# USB.net
KiCad netlist of a schematic drawn in Altium Designer
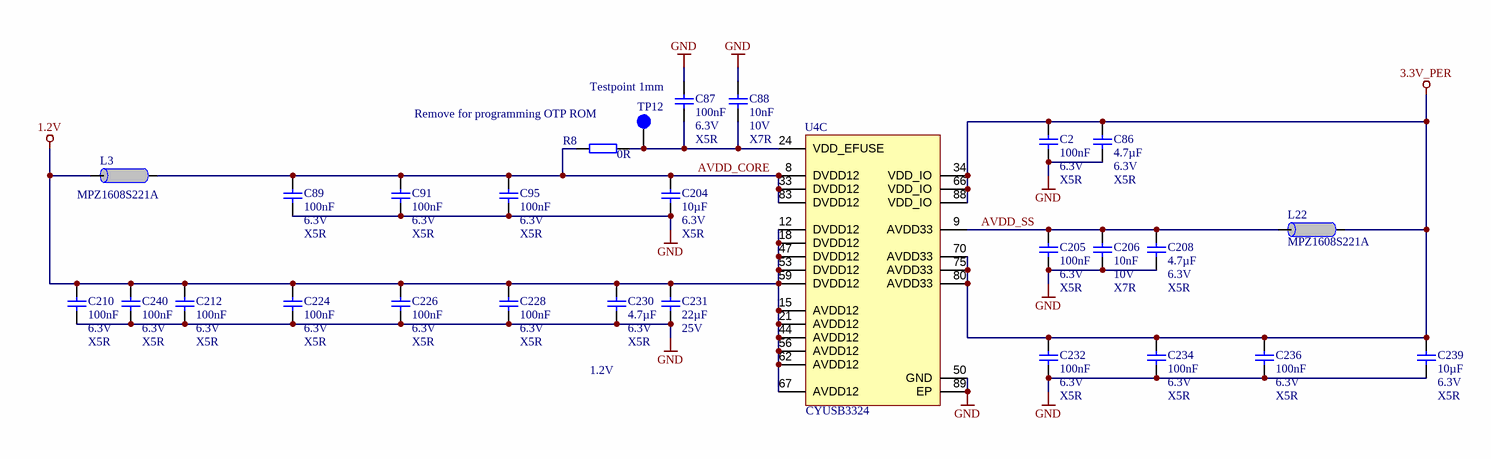
[diagram p0: USB.schdoc]

(export (version "E")
  (design (tool "Eeschema 10.0.6"))
  (components
    (comp (ref "C2")
      (value "100nF")
      (footprint "CAPC0603X33N")
      (description "KON 100nF 6.3V X5R SMD 10%")
      (fields
        (field (name "VOLTAGE") "6.3V")
        (field (name "TECHNOLOGY") "X5R")
        (field (name "TOLERANCE") "10%")
      )
      (libsource (lib "TE") (part "CAP-NP"))
    )
    (comp (ref "C86")
      (value "4.7µF")
      (footprint "CAPC1005X60N")
      (description "KON 4.7µF 6.3V X5R SMD 20%")
      (fields
        (field (name "VOLTAGE") "6.3V")
        (field (name "TECHNOLOGY") "X5R")
        (field (name "TOLERANCE") "20%")
      )
      (libsource (lib "TE") (part "CAP-NP"))
    )
    (comp (ref "C87")
      (value "100nF")
      (footprint "CAPC0603X33N")
      (description "KON 100nF 6.3V X5R SMD 10%")
      (fields
        (field (name "VOLTAGE") "6.3V")
        (field (name "TECHNOLOGY") "X5R")
        (field (name "TOLERANCE") "10%")
      )
      (libsource (lib "TE") (part "CAP-NP"))
    )
    (comp (ref "C88")
      (value "10nF")
      (footprint "CAPC0603X33N")
      (description "KON 10nF X7R 10V SMD 10%")
      (fields
        (field (name "VOLTAGE") "10V")
        (field (name "TECHNOLOGY") "X7R")
        (field (name "TOLERANCE") "10%")
      )
      (libsource (lib "TE") (part "CAP-NP"))
    )
    (comp (ref "C89")
      (value "100nF")
      (footprint "CAPC0603X33N")
      (description "KON 100nF 6.3V X5R SMD 10%")
      (fields
        (field (name "VOLTAGE") "6.3V")
        (field (name "TECHNOLOGY") "X5R")
        (field (name "TOLERANCE") "10%")
      )
      (libsource (lib "TE") (part "CAP-NP"))
    )
    (comp (ref "C91")
      (value "100nF")
      (footprint "CAPC0603X33N")
      (description "KON 100nF 6.3V X5R SMD 10%")
      (fields
        (field (name "VOLTAGE") "6.3V")
        (field (name "TECHNOLOGY") "X5R")
        (field (name "TOLERANCE") "10%")
      )
      (libsource (lib "TE") (part "CAP-NP"))
    )
    (comp (ref "C95")
      (value "100nF")
      (footprint "CAPC0603X33N")
      (description "KON 100nF 6.3V X5R SMD 10%")
      (fields
        (field (name "VOLTAGE") "6.3V")
        (field (name "TECHNOLOGY") "X5R")
        (field (name "TOLERANCE") "10%")
      )
      (libsource (lib "TE") (part "CAP-NP"))
    )
    (comp (ref "C204")
      (value "10µF")
      (footprint "CAPC1608X90N")
      (description "KON 10µF 6,3V X5R SMD")
      (fields (field (name "VOLTAGE") "6.3V") (field (name "TECHNOLOGY") "X5R"))
      (libsource (lib "TE") (part "CAP-NP"))
    )
    (comp (ref "C205")
      (value "100nF")
      (footprint "CAPC0603X33N")
      (description "KON 100nF 6.3V X5R SMD 10%")
      (fields
        (field (name "VOLTAGE") "6.3V")
        (field (name "TECHNOLOGY") "X5R")
        (field (name "TOLERANCE") "10%")
      )
      (libsource (lib "TE") (part "CAP-NP"))
    )
    (comp (ref "C206")
      (value "10nF")
      (footprint "CAPC0603X33N")
      (description "KON 10nF X7R 10V SMD 10%")
      (fields
        (field (name "VOLTAGE") "10V")
        (field (name "TECHNOLOGY") "X7R")
        (field (name "TOLERANCE") "10%")
      )
      (libsource (lib "TE") (part "CAP-NP"))
    )
    (comp (ref "C208")
      (value "4.7µF")
      (footprint "CAPC1005X60N")
      (description "KON 4.7µF 6.3V X5R SMD 20%")
      (fields
        (field (name "VOLTAGE") "6.3V")
        (field (name "TECHNOLOGY") "X5R")
        (field (name "TOLERANCE") "20%")
      )
      (libsource (lib "TE") (part "CAP-NP"))
    )
    (comp (ref "C210")
      (value "100nF")
      (footprint "CAPC0603X33N")
      (description "KON 100nF 6.3V X5R SMD 10%")
      (fields
        (field (name "VOLTAGE") "6.3V")
        (field (name "TECHNOLOGY") "X5R")
        (field (name "TOLERANCE") "10%")
      )
      (libsource (lib "TE") (part "CAP-NP"))
    )
    (comp (ref "C212")
      (value "100nF")
      (footprint "CAPC0603X33N")
      (description "KON 100nF 6.3V X5R SMD 10%")
      (fields
        (field (name "VOLTAGE") "6.3V")
        (field (name "TECHNOLOGY") "X5R")
        (field (name "TOLERANCE") "10%")
      )
      (libsource (lib "TE") (part "CAP-NP"))
    )
    (comp (ref "C224")
      (value "100nF")
      (footprint "CAPC0603X33N")
      (description "KON 100nF 6.3V X5R SMD 10%")
      (fields
        (field (name "VOLTAGE") "6.3V")
        (field (name "TECHNOLOGY") "X5R")
        (field (name "TOLERANCE") "10%")
      )
      (libsource (lib "TE") (part "CAP-NP"))
    )
    (comp (ref "C226")
      (value "100nF")
      (footprint "CAPC0603X33N")
      (description "KON 100nF 6.3V X5R SMD 10%")
      (fields
        (field (name "VOLTAGE") "6.3V")
        (field (name "TECHNOLOGY") "X5R")
        (field (name "TOLERANCE") "10%")
      )
      (libsource (lib "TE") (part "CAP-NP"))
    )
    (comp (ref "C228")
      (value "100nF")
      (footprint "CAPC0603X33N")
      (description "KON 100nF 6.3V X5R SMD 10%")
      (fields
        (field (name "VOLTAGE") "6.3V")
        (field (name "TECHNOLOGY") "X5R")
        (field (name "TOLERANCE") "10%")
      )
      (libsource (lib "TE") (part "CAP-NP"))
    )
    (comp (ref "C230")
      (value "4.7µF")
      (footprint "CAPC1005X60N")
      (description "KON 4.7µF 6.3V X5R SMD 20%")
      (fields
        (field (name "VOLTAGE") "6.3V")
        (field (name "TECHNOLOGY") "X5R")
        (field (name "TOLERANCE") "20%")
      )
      (libsource (lib "TE") (part "CAP-NP"))
    )
    (comp (ref "C231")
      (value "22µF")
      (footprint "CAPC3216X180N")
      (description "KON 22µF X5R 25V SMD 10%")
      (fields (field (name "VOLTAGE") "25V") (field (name "TOLERANCE") "10%"))
      (libsource (lib "TE") (part "CAP-NP"))
    )
    (comp (ref "C232")
      (value "100nF")
      (footprint "CAPC0603X33N")
      (description "KON 100nF 6.3V X5R SMD 10%")
      (fields
        (field (name "VOLTAGE") "6.3V")
        (field (name "TECHNOLOGY") "X5R")
        (field (name "TOLERANCE") "10%")
      )
      (libsource (lib "TE") (part "CAP-NP"))
    )
    (comp (ref "C234")
      (value "100nF")
      (footprint "CAPC0603X33N")
      (description "KON 100nF 6.3V X5R SMD 10%")
      (fields
        (field (name "VOLTAGE") "6.3V")
        (field (name "TECHNOLOGY") "X5R")
        (field (name "TOLERANCE") "10%")
      )
      (libsource (lib "TE") (part "CAP-NP"))
    )
    (comp (ref "C236")
      (value "100nF")
      (footprint "CAPC0603X33N")
      (description "KON 100nF 6.3V X5R SMD 10%")
      (fields
        (field (name "VOLTAGE") "6.3V")
        (field (name "TECHNOLOGY") "X5R")
        (field (name "TOLERANCE") "10%")
      )
      (libsource (lib "TE") (part "CAP-NP"))
    )
    (comp (ref "C239")
      (value "10µF")
      (footprint "CAPC1608X90N")
      (description "KON 10µF 6,3V X5R SMD")
      (fields (field (name "VOLTAGE") "6.3V") (field (name "TECHNOLOGY") "X5R"))
      (libsource (lib "TE") (part "CAP-NP"))
    )
    (comp (ref "C240")
      (value "100nF")
      (footprint "CAPC0603X33N")
      (description "KON 100nF 6.3V X5R SMD 10%")
      (fields
        (field (name "VOLTAGE") "6.3V")
        (field (name "TECHNOLOGY") "X5R")
        (field (name "TOLERANCE") "10%")
      )
      (libsource (lib "TE") (part "CAP-NP"))
    )
    (comp (ref "L3")
      (value "MPZ1608S221A")
      (footprint "INDC1608X95N")
      (description "Ferritdurchführung MPZ1608S221A")
      (libsource (lib "TE") (part "Ferritperle"))
    )
    (comp (ref "L22")
      (value "MPZ1608S221A")
      (footprint "INDC1608X95N")
      (description "Ferritdurchführung MPZ1608S221A")
      (libsource (lib "") (part "Ferritperle_1"))
    )
    (comp (ref "R8")
      (value "0R")
      (footprint "RESC1005X40N")
      (description "WID SMD 0R")
      (fields (field (name "TOLERANCE") "1%"))
      (libsource (lib "TE") (part "RES"))
    )
    (comp (ref "TP12") (value "Testpoint 1mm") (footprint "TP_1mm") (libsource (lib "TE") (part "TP")))
    (comp (ref "U4")
      (value "CYUSB3324")
      (footprint "QFN40P10X10X1-89T530")
      (description "CYUSB3324-88LTXC USB 3.0 Hub")
      (libsource (lib "TE") (part "CYUSB3324"))
    )
  )
  (nets
    (net (code "1") (name "/AVDD_CORE") (class "Default")
      (node (ref "C204") (pin "1") (pinfunction "1_1") (pintype "passive"))
      (node (ref "C89") (pin "2") (pinfunction "2_2") (pintype "passive"))
      (node (ref "C91") (pin "2") (pinfunction "2_2") (pintype "passive"))
      (node (ref "C95") (pin "2") (pinfunction "2_2") (pintype "passive"))
      (node (ref "L3") (pin "1") (pinfunction "1_1") (pintype "passive"))
      (node (ref "R8") (pin "2") (pinfunction "2_2") (pintype "passive"))
      (node (ref "U4") (pin "33") (pinfunction "DVDD12_33") (pintype "power_in"))
      (node (ref "U4") (pin "8") (pinfunction "DVDD12_8") (pintype "power_in"))
      (node (ref "U4") (pin "83") (pinfunction "DVDD12_83") (pintype "power_in"))
    )
    (net (code "2") (name "/AVDD_SS") (class "Default")
      (node (ref "C205") (pin "1") (pinfunction "1_1") (pintype "passive"))
      (node (ref "C206") (pin "1") (pinfunction "1_1") (pintype "passive"))
      (node (ref "C208") (pin "2") (pinfunction "2_2") (pintype "passive"))
      (node (ref "L22") (pin "2") (pinfunction "2_2") (pintype "passive"))
      (node (ref "U4") (pin "9") (pinfunction "AVDD33_9") (pintype "power_in"))
    )
    (net (code "3") (name "1.2V") (class "Default")
      (node (ref "C210") (pin "2") (pinfunction "2_2") (pintype "passive"))
      (node (ref "C212") (pin "2") (pinfunction "2_2") (pintype "passive"))
      (node (ref "C224") (pin "2") (pinfunction "2_2") (pintype "passive"))
      (node (ref "C226") (pin "2") (pinfunction "2_2") (pintype "passive"))
      (node (ref "C228") (pin "2") (pinfunction "2_2") (pintype "passive"))
      (node (ref "C230") (pin "1") (pinfunction "1_1") (pintype "passive"))
      (node (ref "C231") (pin "2") (pinfunction "2_2") (pintype "passive"))
      (node (ref "C240") (pin "2") (pinfunction "2_2") (pintype "passive"))
      (node (ref "L3") (pin "2") (pinfunction "2_2") (pintype "passive"))
      (node (ref "U4") (pin "12") (pinfunction "DVDD12_12") (pintype "power_in"))
      (node (ref "U4") (pin "15") (pinfunction "AVDD12_15") (pintype "power_in"))
      (node (ref "U4") (pin "18") (pinfunction "DVDD12_18") (pintype "power_in"))
      (node (ref "U4") (pin "21") (pinfunction "AVDD12_21") (pintype "power_in"))
      (node (ref "U4") (pin "44") (pinfunction "AVDD12_44") (pintype "power_in"))
      (node (ref "U4") (pin "47") (pinfunction "DVDD12_47") (pintype "power_in"))
      (node (ref "U4") (pin "53") (pinfunction "DVDD12_53") (pintype "power_in"))
      (node (ref "U4") (pin "56") (pinfunction "AVDD12_56") (pintype "power_in"))
      (node (ref "U4") (pin "59") (pinfunction "DVDD12_59") (pintype "power_in"))
      (node (ref "U4") (pin "62") (pinfunction "AVDD12_62") (pintype "power_in"))
      (node (ref "U4") (pin "67") (pinfunction "AVDD12_67") (pintype "power_in"))
    )
    (net (code "4") (name "3.3V_PER") (class "Default")
      (node (ref "C2") (pin "1") (pinfunction "1_1") (pintype "passive"))
      (node (ref "C232") (pin "2") (pinfunction "2_2") (pintype "passive"))
      (node (ref "C234") (pin "2") (pinfunction "2_2") (pintype "passive"))
      (node (ref "C236") (pin "2") (pinfunction "2_2") (pintype "passive"))
      (node (ref "C239") (pin "1") (pinfunction "1_1") (pintype "passive"))
      (node (ref "C86") (pin "2") (pinfunction "2_2") (pintype "passive"))
      (node (ref "L22") (pin "1") (pinfunction "1_1") (pintype "passive"))
      (node (ref "U4") (pin "34") (pinfunction "VDD_IO_34") (pintype "power_in"))
      (node (ref "U4") (pin "66") (pinfunction "VDD_IO_66") (pintype "power_in"))
      (node (ref "U4") (pin "70") (pinfunction "AVDD33_70") (pintype "power_in"))
      (node (ref "U4") (pin "75") (pinfunction "AVDD33_75") (pintype "power_in"))
      (node (ref "U4") (pin "80") (pinfunction "AVDD33_80") (pintype "power_in"))
      (node (ref "U4") (pin "88") (pinfunction "VDD_IO_88") (pintype "power_in"))
    )
    (net (code "5") (name "GND") (class "Default")
      (node (ref "C2") (pin "2") (pinfunction "2_2") (pintype "passive"))
      (node (ref "C204") (pin "2") (pinfunction "2_2") (pintype "passive"))
      (node (ref "C205") (pin "2") (pinfunction "2_2") (pintype "passive"))
      (node (ref "C206") (pin "2") (pinfunction "2_2") (pintype "passive"))
      (node (ref "C208") (pin "1") (pinfunction "1_1") (pintype "passive"))
      (node (ref "C210") (pin "1") (pinfunction "1_1") (pintype "passive"))
      (node (ref "C212") (pin "1") (pinfunction "1_1") (pintype "passive"))
      (node (ref "C224") (pin "1") (pinfunction "1_1") (pintype "passive"))
      (node (ref "C226") (pin "1") (pinfunction "1_1") (pintype "passive"))
      (node (ref "C228") (pin "1") (pinfunction "1_1") (pintype "passive"))
      (node (ref "C230") (pin "2") (pinfunction "2_2") (pintype "passive"))
      (node (ref "C231") (pin "1") (pinfunction "1_1") (pintype "passive"))
      (node (ref "C232") (pin "1") (pinfunction "1_1") (pintype "passive"))
      (node (ref "C234") (pin "1") (pinfunction "1_1") (pintype "passive"))
      (node (ref "C236") (pin "1") (pinfunction "1_1") (pintype "passive"))
      (node (ref "C239") (pin "2") (pinfunction "2_2") (pintype "passive"))
      (node (ref "C240") (pin "1") (pinfunction "1_1") (pintype "passive"))
      (node (ref "C86") (pin "1") (pinfunction "1_1") (pintype "passive"))
      (node (ref "C87") (pin "2") (pinfunction "2_2") (pintype "passive"))
      (node (ref "C88") (pin "2") (pinfunction "2_2") (pintype "passive"))
      (node (ref "C89") (pin "1") (pinfunction "1_1") (pintype "passive"))
      (node (ref "C91") (pin "1") (pinfunction "1_1") (pintype "passive"))
      (node (ref "C95") (pin "1") (pinfunction "1_1") (pintype "passive"))
      (node (ref "U4") (pin "50") (pinfunction "GND_50") (pintype "power_in"))
      (node (ref "U4") (pin "89") (pinfunction "EP_89") (pintype "power_in"))
    )
    (net (code "6") (name "Net-(U4C-VDD_EFUSE)") (class "Default")
      (node (ref "C87") (pin "1") (pinfunction "1_1") (pintype "passive"))
      (node (ref "C88") (pin "1") (pinfunction "1_1") (pintype "passive"))
      (node (ref "R8") (pin "1") (pinfunction "1_1") (pintype "passive"))
      (node (ref "TP12") (pin "1") (pintype "passive"))
      (node (ref "U4") (pin "24") (pinfunction "VDD_EFUSE_24") (pintype "power_in"))
    )
  )
)
